# SigGenerator.net
KiCad netlist of a schematic drawn in EAGLE
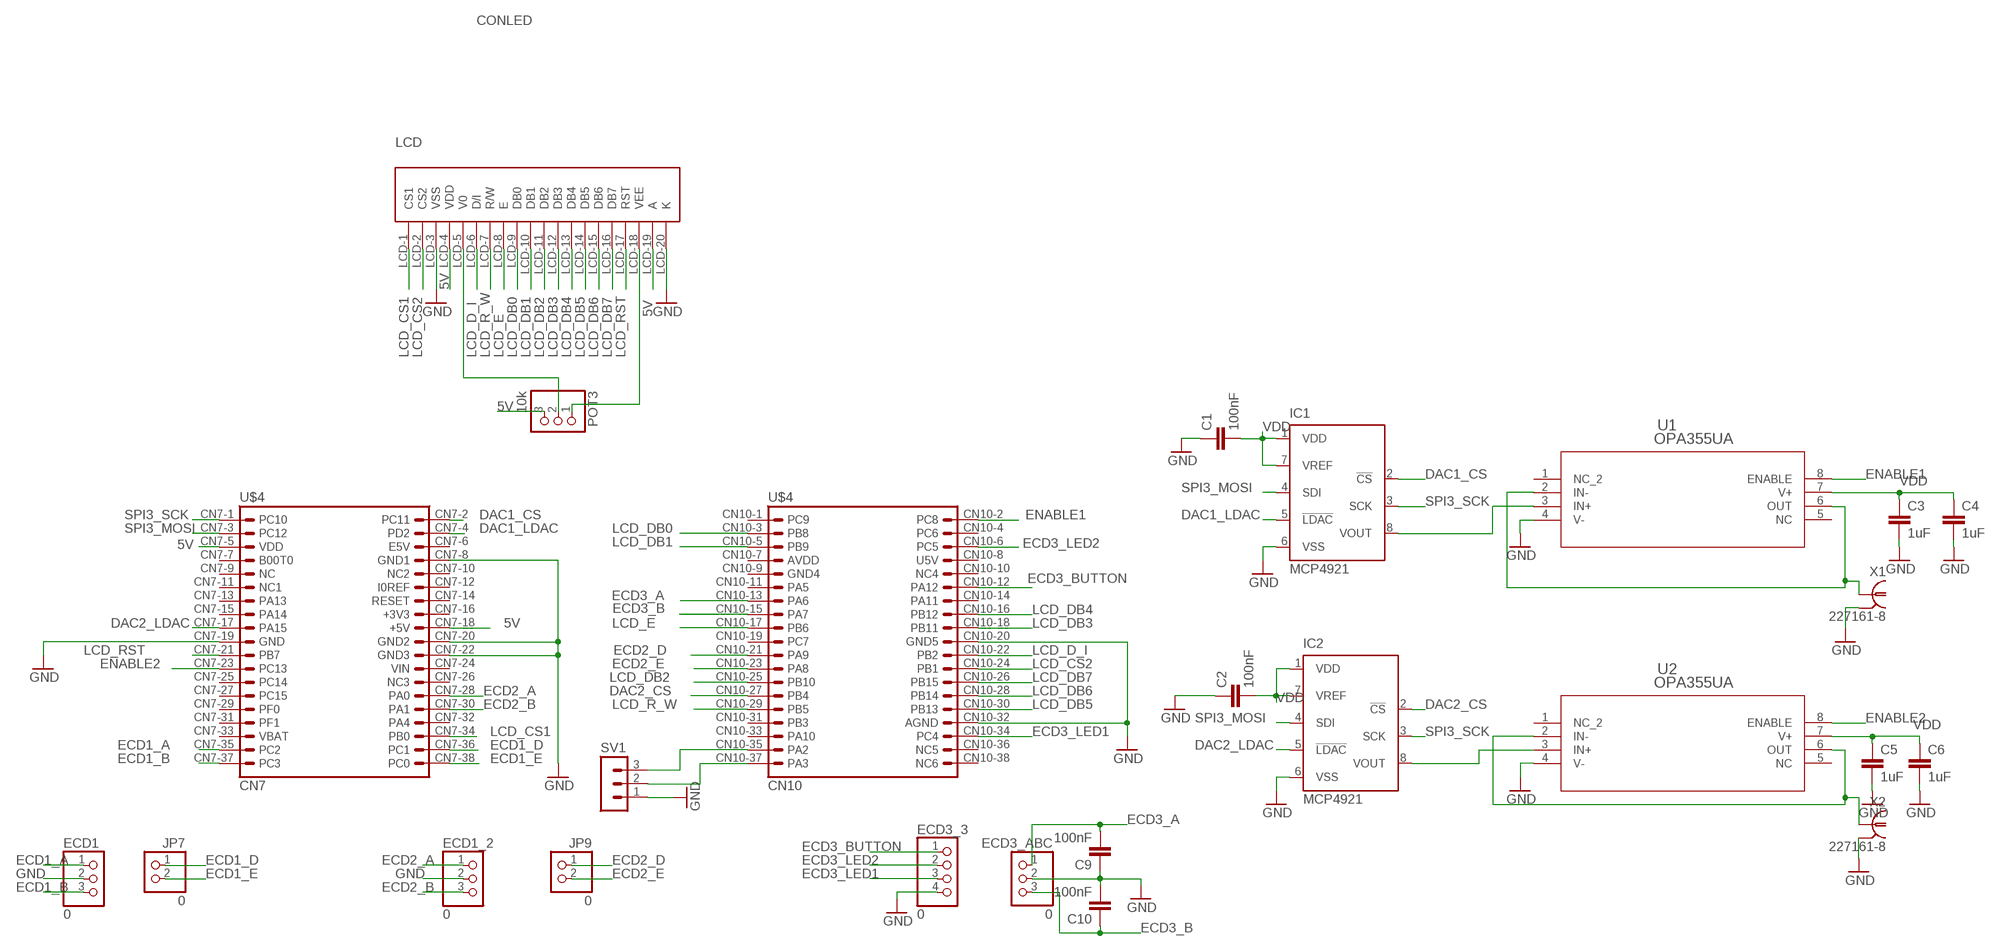
[diagram p0: schematic, sheet 1]
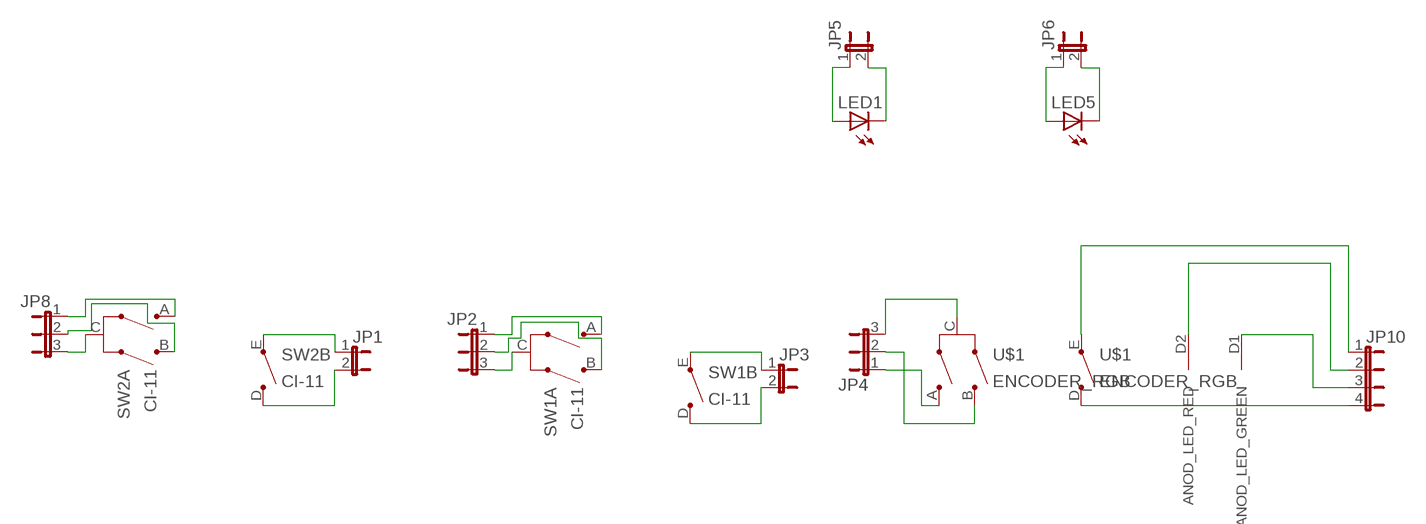
[diagram p1: schematic, sheet 2]

(export (version "E")
  (design (tool "Eeschema 10.0.6"))
  (components
    (comp (ref "JP1")
      (value "JP1E")
      (footprint "eagle-import:JP1")
      (libsource (lib "eagle-import") (part "JP1E"))
    )
    (comp (ref "JP2")
      (value "JP2E")
      (footprint "eagle-import:JP2")
      (libsource (lib "eagle-import") (part "JP2E"))
    )
    (comp (ref "JP3")
      (value "JP1E")
      (footprint "eagle-import:JP1")
      (libsource (lib "eagle-import") (part "JP1E"))
    )
    (comp (ref "JP4")
      (value "JP2E")
      (footprint "eagle-import:JP2")
      (libsource (lib "eagle-import") (part "JP2E"))
    )
    (comp (ref "JP5")
      (value "JP1E")
      (footprint "eagle-import:JP1")
      (libsource (lib "eagle-import") (part "JP1E"))
    )
    (comp (ref "JP6")
      (value "JP1E")
      (footprint "eagle-import:JP1")
      (libsource (lib "eagle-import") (part "JP1E"))
    )
    (comp (ref "JP8")
      (value "JP2E")
      (footprint "eagle-import:JP2")
      (libsource (lib "eagle-import") (part "JP2E"))
    )
    (comp (ref "JP10")
      (value "JP4E")
      (footprint "eagle-import:JP4")
      (libsource (lib "eagle-import") (part "JP4E"))
    )
    (comp (ref "LED1")
      (value "LEDSQR2X5")
      (footprint "eagle-import:LED2X5")
      (libsource (lib "eagle-import") (part "LEDSQR2X5"))
    )
    (comp (ref "LED5")
      (value "LEDSQR2X5")
      (footprint "eagle-import:LED2X5")
      (libsource (lib "eagle-import") (part "LEDSQR2X5"))
    )
    (comp (ref "SW1")
      (value "CI-11")
      (footprint "eagle-import:CI-11")
      (libsource (lib "eagle-import") (part "CI-11"))
    )
    (comp (ref "SW2")
      (value "CI-11")
      (footprint "eagle-import:CI-11")
      (libsource (lib "eagle-import") (part "CI-11"))
    )
    (comp (ref "U$1")
      (value "ENCODER_RGB")
      (footprint "eagle-import:ENCODER_RGB")
      (libsource (lib "eagle-import") (part "ENCODER_RGB"))
    )
    (comp (ref "C1")
      (value "100nF")
      (footprint "eagle-import:C2.5-3")
      (libsource (lib "eagle-import") (part "C2,5-3"))
    )
    (comp (ref "C2")
      (value "100nF")
      (footprint "eagle-import:C2.5-3")
      (libsource (lib "eagle-import") (part "C2,5-3"))
    )
    (comp (ref "C3")
      (value "1uF")
      (footprint "eagle-import:C2.5-3")
      (libsource (lib "eagle-import") (part "C2,5-3"))
    )
    (comp (ref "C4")
      (value "1uF")
      (footprint "eagle-import:C2.5-3")
      (libsource (lib "eagle-import") (part "C2,5-3"))
    )
    (comp (ref "C5")
      (value "1uF")
      (footprint "eagle-import:C2.5-3")
      (libsource (lib "eagle-import") (part "C2,5-3"))
    )
    (comp (ref "C6")
      (value "1uF")
      (footprint "eagle-import:C2.5-3")
      (libsource (lib "eagle-import") (part "C2,5-3"))
    )
    (comp (ref "C9")
      (value "100nF")
      (footprint "eagle-import:C2.5-3")
      (libsource (lib "eagle-import") (part "C2,5-3"))
    )
    (comp (ref "C10")
      (value "100nF")
      (footprint "eagle-import:C2.5-3")
      (libsource (lib "eagle-import") (part "C2,5-3"))
    )
    (comp (ref "ECD1")
      (value "0")
      (footprint "eagle-import:1X03")
      (libsource (lib "eagle-import") (part "PINHD-1X3"))
    )
    (comp (ref "ECD1_2")
      (value "0")
      (footprint "eagle-import:1X03")
      (libsource (lib "eagle-import") (part "PINHD-1X3"))
    )
    (comp (ref "ECD3_3")
      (value "0")
      (footprint "eagle-import:1X04")
      (libsource (lib "eagle-import") (part "PINHD-1X4"))
    )
    (comp (ref "ECD3_ABC")
      (value "0")
      (footprint "eagle-import:1X03")
      (libsource (lib "eagle-import") (part "PINHD-1X3"))
    )
    (comp (ref "IC1")
      (value "MCP4921")
      (footprint "eagle-import:DIL8")
      (libsource (lib "eagle-import") (part "MCP4921"))
    )
    (comp (ref "IC2")
      (value "MCP4921")
      (footprint "eagle-import:DIL8")
      (libsource (lib "eagle-import") (part "MCP4921"))
    )
    (comp (ref "JP7")
      (value "0")
      (footprint "eagle-import:1X02")
      (libsource (lib "eagle-import") (part "PINHD-1X2"))
    )
    (comp (ref "JP9")
      (value "0")
      (footprint "eagle-import:1X02")
      (libsource (lib "eagle-import") (part "PINHD-1X2"))
    )
    (comp (ref "LCD")
      (value "CONLED")
      (footprint "eagle-import:CONLCD")
      (libsource (lib "eagle-import") (part "CONLED"))
    )
    (comp (ref "POT3")
      (value "10k")
      (footprint "eagle-import:1X03")
      (libsource (lib "eagle-import") (part "PINHD-1X3"))
    )
    (comp (ref "SV1")
      (value "MA03-1")
      (footprint "eagle-import:MA03-1")
      (libsource (lib "eagle-import") (part "MA03-1"))
    )
    (comp (ref "U$4")
      (value "STM_MORPHO")
      (footprint "eagle-import:STM")
      (libsource (lib "eagle-import") (part "STM_MORPHO"))
    )
    (comp (ref "U1")
      (value "OPA355UA")
      (footprint "eagle-import:D8")
      (libsource (lib "eagle-import") (part "OPA355UA"))
    )
    (comp (ref "U2")
      (value "OPA355UA")
      (footprint "eagle-import:D8")
      (libsource (lib "eagle-import") (part "OPA355UA"))
    )
    (comp (ref "X1")
      (value "227161-8")
      (footprint "eagle-import:AMP_227161")
      (libsource (lib "eagle-import") (part "?227161-8"))
    )
    (comp (ref "X2")
      (value "227161-8")
      (footprint "eagle-import:AMP_227161")
      (libsource (lib "eagle-import") (part "?227161-8"))
    )
  )
  (nets
    (net (code "1") (name "5V") (class "Default")
      (node (ref "LCD") (pin "LCD-19") (pinfunction "A_LCD-19") (pintype "bidirectional"))
      (node (ref "LCD") (pin "LCD-4") (pinfunction "VDD_LCD-4") (pintype "bidirectional"))
      (node (ref "POT3") (pin "3") (pinfunction "3_3") (pintype "passive"))
      (node (ref "U$4") (pin "CN7-18") (pinfunction "+5V_CN7-18") (pintype "bidirectional"))
      (node (ref "U$4") (pin "CN7-5") (pinfunction "VDD_CN7-5") (pintype "bidirectional"))
    )
    (net (code "2") (name "DAC1_CS") (class "Default")
      (node (ref "IC1") (pin "2") (pinfunction "~{CS}_2") (pintype "input"))
      (node (ref "U$4") (pin "CN7-2") (pinfunction "PC11_CN7-2") (pintype "bidirectional"))
    )
    (net (code "3") (name "DAC1_LDAC") (class "Default")
      (node (ref "IC1") (pin "5") (pinfunction "~{LDAC}_5") (pintype "input"))
      (node (ref "U$4") (pin "CN7-4") (pinfunction "PD2_CN7-4") (pintype "bidirectional"))
    )
    (net (code "4") (name "DAC2_CS") (class "Default")
      (node (ref "IC2") (pin "2") (pinfunction "~{CS}_2") (pintype "input"))
      (node (ref "U$4") (pin "CN10-27") (pinfunction "PB4_CN10-27") (pintype "bidirectional"))
    )
    (net (code "5") (name "DAC2_LDAC") (class "Default")
      (node (ref "IC2") (pin "5") (pinfunction "~{LDAC}_5") (pintype "input"))
      (node (ref "U$4") (pin "CN7-17") (pinfunction "PA15_CN7-17") (pintype "bidirectional"))
    )
    (net (code "6") (name "ECD1_A") (class "Default")
      (node (ref "ECD1") (pin "1") (pinfunction "1_1") (pintype "passive"))
      (node (ref "U$4") (pin "CN7-35") (pinfunction "PC2_CN7-35") (pintype "bidirectional"))
    )
    (net (code "7") (name "ECD1_B") (class "Default")
      (node (ref "ECD1") (pin "3") (pinfunction "3_3") (pintype "passive"))
      (node (ref "U$4") (pin "CN7-37") (pinfunction "PC3_CN7-37") (pintype "bidirectional"))
    )
    (net (code "8") (name "ECD1_D") (class "Default")
      (node (ref "JP7") (pin "1") (pinfunction "1_1") (pintype "passive"))
      (node (ref "U$4") (pin "CN7-36") (pinfunction "PC1_CN7-36") (pintype "bidirectional"))
    )
    (net (code "9") (name "ECD1_E") (class "Default")
      (node (ref "JP7") (pin "2") (pinfunction "2_2") (pintype "passive"))
      (node (ref "U$4") (pin "CN7-38") (pinfunction "PC0_CN7-38") (pintype "bidirectional"))
    )
    (net (code "10") (name "ECD2_A") (class "Default")
      (node (ref "ECD1_2") (pin "1") (pinfunction "1_1") (pintype "passive"))
      (node (ref "U$4") (pin "CN7-28") (pinfunction "PA0_CN7-28") (pintype "bidirectional"))
    )
    (net (code "11") (name "ECD2_B") (class "Default")
      (node (ref "ECD1_2") (pin "3") (pinfunction "3_3") (pintype "passive"))
      (node (ref "U$4") (pin "CN7-30") (pinfunction "PA1_CN7-30") (pintype "bidirectional"))
    )
    (net (code "12") (name "ECD2_D") (class "Default")
      (node (ref "JP9") (pin "1") (pinfunction "1_1") (pintype "passive"))
      (node (ref "U$4") (pin "CN10-21") (pinfunction "PA9_CN10-21") (pintype "bidirectional"))
    )
    (net (code "13") (name "ECD2_E") (class "Default")
      (node (ref "JP9") (pin "2") (pinfunction "2_2") (pintype "passive"))
      (node (ref "U$4") (pin "CN10-23") (pinfunction "PA8_CN10-23") (pintype "bidirectional"))
    )
    (net (code "14") (name "ECD3_A") (class "Default")
      (node (ref "C9") (pin "2") (pinfunction "2_2") (pintype "passive"))
      (node (ref "ECD3_ABC") (pin "1") (pinfunction "1_1") (pintype "passive"))
      (node (ref "U$4") (pin "CN10-13") (pinfunction "PA6_CN10-13") (pintype "bidirectional"))
    )
    (net (code "15") (name "ECD3_B") (class "Default")
      (node (ref "C10") (pin "1") (pinfunction "1_1") (pintype "passive"))
      (node (ref "ECD3_ABC") (pin "3") (pinfunction "3_3") (pintype "passive"))
      (node (ref "U$4") (pin "CN10-15") (pinfunction "PA7_CN10-15") (pintype "bidirectional"))
    )
    (net (code "16") (name "ECD3_BUTTON") (class "Default")
      (node (ref "ECD3_3") (pin "1") (pinfunction "1_1") (pintype "passive"))
      (node (ref "U$4") (pin "CN10-12") (pinfunction "PA12_CN10-12") (pintype "bidirectional"))
    )
    (net (code "17") (name "ECD3_LED1") (class "Default")
      (node (ref "ECD3_3") (pin "3") (pinfunction "3_3") (pintype "passive"))
      (node (ref "U$4") (pin "CN10-34") (pinfunction "PC4_CN10-34") (pintype "bidirectional"))
    )
    (net (code "18") (name "ECD3_LED2") (class "Default")
      (node (ref "ECD3_3") (pin "2") (pinfunction "2_2") (pintype "passive"))
      (node (ref "U$4") (pin "CN10-6") (pinfunction "PC5_CN10-6") (pintype "bidirectional"))
    )
    (net (code "19") (name "ENABLE1") (class "Default")
      (node (ref "U$4") (pin "CN10-2") (pinfunction "PC8_CN10-2") (pintype "bidirectional"))
      (node (ref "U1") (pin "8") (pinfunction "ENABLE_8") (pintype "passive"))
    )
    (net (code "20") (name "ENABLE2") (class "Default")
      (node (ref "U$4") (pin "CN7-23") (pinfunction "PC13_CN7-23") (pintype "bidirectional"))
      (node (ref "U2") (pin "8") (pinfunction "ENABLE_8") (pintype "passive"))
    )
    (net (code "21") (name "GND") (class "Default")
      (node (ref "C1") (pin "1") (pinfunction "1_1") (pintype "passive"))
      (node (ref "C10") (pin "2") (pinfunction "2_2") (pintype "passive"))
      (node (ref "C2") (pin "1") (pinfunction "1_1") (pintype "passive"))
      (node (ref "C3") (pin "2") (pinfunction "2_2") (pintype "passive"))
      (node (ref "C4") (pin "2") (pinfunction "2_2") (pintype "passive"))
      (node (ref "C5") (pin "2") (pinfunction "2_2") (pintype "passive"))
      (node (ref "C6") (pin "2") (pinfunction "2_2") (pintype "passive"))
      (node (ref "C9") (pin "1") (pinfunction "1_1") (pintype "passive"))
      (node (ref "ECD1") (pin "2") (pinfunction "2_2") (pintype "passive"))
      (node (ref "ECD1_2") (pin "2") (pinfunction "2_2") (pintype "passive"))
      (node (ref "ECD3_3") (pin "4") (pinfunction "4_4") (pintype "passive"))
      (node (ref "ECD3_ABC") (pin "2") (pinfunction "2_2") (pintype "passive"))
      (node (ref "IC1") (pin "6") (pinfunction "VSS_6") (pintype "power_in"))
      (node (ref "IC2") (pin "6") (pinfunction "VSS_6") (pintype "power_in"))
      (node (ref "LCD") (pin "LCD-20") (pinfunction "K_LCD-20") (pintype "bidirectional"))
      (node (ref "LCD") (pin "LCD-3") (pinfunction "VSS_LCD-3") (pintype "bidirectional"))
      (node (ref "SV1") (pin "1") (pinfunction "1_1") (pintype "passive"))
      (node (ref "U$4") (pin "CN10-20") (pinfunction "GND5_CN10-20") (pintype "bidirectional"))
      (node (ref "U$4") (pin "CN10-32") (pinfunction "AGND_CN10-32") (pintype "bidirectional"))
      (node (ref "U$4") (pin "CN7-19") (pinfunction "GND_CN7-19") (pintype "bidirectional"))
      (node (ref "U$4") (pin "CN7-20") (pinfunction "GND2_CN7-20") (pintype "bidirectional"))
      (node (ref "U$4") (pin "CN7-22") (pinfunction "GND3_CN7-22") (pintype "bidirectional"))
      (node (ref "U$4") (pin "CN7-8") (pinfunction "GND1_CN7-8") (pintype "bidirectional"))
      (node (ref "U1") (pin "4") (pinfunction "V-_4") (pintype "power_in"))
      (node (ref "U2") (pin "4") (pinfunction "V-_4") (pintype "power_in"))
      (node (ref "X1") (pin "2") (pinfunction "2_2") (pintype "passive"))
      (node (ref "X2") (pin "2") (pinfunction "2_2") (pintype "passive"))
    )
    (net (code "22") (name "GND3") (class "Default")
      (node (ref "JP1") (pin "2") (pinfunction "2_2") (pintype "passive"))
      (node (ref "JP10") (pin "4") (pinfunction "4_4") (pintype "passive"))
      (node (ref "JP2") (pin "3") (pinfunction "3_3") (pintype "passive"))
      (node (ref "JP3") (pin "2") (pinfunction "2_2") (pintype "passive"))
      (node (ref "JP4") (pin "3") (pinfunction "3_3") (pintype "passive"))
      (node (ref "SW1") (pin "C") (pinfunction "C_C") (pintype "passive"))
      (node (ref "SW1") (pin "D") (pinfunction "D_D") (pintype "passive"))
      (node (ref "SW2") (pin "D") (pinfunction "D_D") (pintype "passive"))
      (node (ref "U$1") (pin "C") (pinfunction "C_C") (pintype "passive"))
      (node (ref "U$1") (pin "D") (pinfunction "1_D") (pintype "passive"))
    )
    (net (code "23") (name "LCD_CS1") (class "Default")
      (node (ref "LCD") (pin "LCD-1") (pinfunction "CS1_LCD-1") (pintype "bidirectional"))
      (node (ref "U$4") (pin "CN7-34") (pinfunction "PB0_CN7-34") (pintype "bidirectional"))
    )
    (net (code "24") (name "LCD_CS2") (class "Default")
      (node (ref "LCD") (pin "LCD-2") (pinfunction "CS2_LCD-2") (pintype "bidirectional"))
      (node (ref "U$4") (pin "CN10-24") (pinfunction "PB1_CN10-24") (pintype "bidirectional"))
    )
    (net (code "25") (name "LCD_DB0") (class "Default")
      (node (ref "LCD") (pin "LCD-9") (pinfunction "DB0_LCD-9") (pintype "bidirectional"))
      (node (ref "U$4") (pin "CN10-3") (pinfunction "PB8_CN10-3") (pintype "bidirectional"))
    )
    (net (code "26") (name "LCD_DB1") (class "Default")
      (node (ref "LCD") (pin "LCD-10") (pinfunction "DB1_LCD-10") (pintype "bidirectional"))
      (node (ref "U$4") (pin "CN10-5") (pinfunction "PB9_CN10-5") (pintype "bidirectional"))
    )
    (net (code "27") (name "LCD_DB2") (class "Default")
      (node (ref "LCD") (pin "LCD-11") (pinfunction "DB2_LCD-11") (pintype "bidirectional"))
      (node (ref "U$4") (pin "CN10-25") (pinfunction "PB10_CN10-25") (pintype "bidirectional"))
    )
    (net (code "28") (name "LCD_DB3") (class "Default")
      (node (ref "LCD") (pin "LCD-12") (pinfunction "DB3_LCD-12") (pintype "bidirectional"))
      (node (ref "U$4") (pin "CN10-18") (pinfunction "PB11_CN10-18") (pintype "bidirectional"))
    )
    (net (code "29") (name "LCD_DB4") (class "Default")
      (node (ref "LCD") (pin "LCD-13") (pinfunction "DB4_LCD-13") (pintype "bidirectional"))
      (node (ref "U$4") (pin "CN10-16") (pinfunction "PB12_CN10-16") (pintype "bidirectional"))
    )
    (net (code "30") (name "LCD_DB5") (class "Default")
      (node (ref "LCD") (pin "LCD-14") (pinfunction "DB5_LCD-14") (pintype "bidirectional"))
      (node (ref "U$4") (pin "CN10-30") (pinfunction "PB13_CN10-30") (pintype "bidirectional"))
    )
    (net (code "31") (name "LCD_DB6") (class "Default")
      (node (ref "LCD") (pin "LCD-15") (pinfunction "DB6_LCD-15") (pintype "bidirectional"))
      (node (ref "U$4") (pin "CN10-28") (pinfunction "PB14_CN10-28") (pintype "bidirectional"))
    )
    (net (code "32") (name "LCD_DB7") (class "Default")
      (node (ref "LCD") (pin "LCD-16") (pinfunction "DB7_LCD-16") (pintype "bidirectional"))
      (node (ref "U$4") (pin "CN10-26") (pinfunction "PB15_CN10-26") (pintype "bidirectional"))
    )
    (net (code "33") (name "LCD_D_I") (class "Default")
      (node (ref "LCD") (pin "LCD-6") (pinfunction "D/I_LCD-6") (pintype "bidirectional"))
      (node (ref "U$4") (pin "CN10-22") (pinfunction "PB2_CN10-22") (pintype "bidirectional"))
    )
    (net (code "34") (name "LCD_E") (class "Default")
      (node (ref "LCD") (pin "LCD-8") (pinfunction "E_LCD-8") (pintype "bidirectional"))
      (node (ref "U$4") (pin "CN10-17") (pinfunction "PB6_CN10-17") (pintype "bidirectional"))
    )
    (net (code "35") (name "LCD_RST") (class "Default")
      (node (ref "LCD") (pin "LCD-17") (pinfunction "RST_LCD-17") (pintype "bidirectional"))
      (node (ref "U$4") (pin "CN7-21") (pinfunction "PB7_CN7-21") (pintype "bidirectional"))
    )
    (net (code "36") (name "LCD_R_W") (class "Default")
      (node (ref "LCD") (pin "LCD-7") (pinfunction "R/W_LCD-7") (pintype "bidirectional"))
      (node (ref "U$4") (pin "CN10-29") (pinfunction "PB5_CN10-29") (pintype "bidirectional"))
    )
    (net (code "37") (name "Net-(IC1-VOUT)") (class "Default")
      (node (ref "IC1") (pin "8") (pinfunction "VOUT_8") (pintype "output"))
      (node (ref "U1") (pin "3") (pinfunction "IN+_3") (pintype "input"))
    )
    (net (code "38") (name "Net-(IC2-VOUT)") (class "Default")
      (node (ref "IC2") (pin "8") (pinfunction "VOUT_8") (pintype "output"))
      (node (ref "U2") (pin "3") (pinfunction "IN+_3") (pintype "input"))
    )
    (net (code "39") (name "Net-(JP1-Pad1)") (class "Default")
      (node (ref "JP1") (pin "1") (pinfunction "1_1") (pintype "passive"))
      (node (ref "SW2") (pin "E") (pinfunction "E_E") (pintype "passive"))
    )
    (net (code "40") (name "Net-(JP2-Pad1)") (class "Default")
      (node (ref "JP2") (pin "1") (pinfunction "1_1") (pintype "passive"))
      (node (ref "SW1") (pin "A") (pinfunction "A_A") (pintype "passive"))
    )
    (net (code "41") (name "Net-(JP2-Pad2)") (class "Default")
      (node (ref "JP2") (pin "2") (pinfunction "2_2") (pintype "passive"))
      (node (ref "SW1") (pin "B") (pinfunction "B_B") (pintype "passive"))
    )
    (net (code "42") (name "Net-(JP3-Pad1)") (class "Default")
      (node (ref "JP3") (pin "1") (pinfunction "1_1") (pintype "passive"))
      (node (ref "SW1") (pin "E") (pinfunction "E_E") (pintype "passive"))
    )
    (net (code "43") (name "Net-(JP4-Pad1)") (class "Default")
      (node (ref "JP4") (pin "1") (pinfunction "1_1") (pintype "passive"))
      (node (ref "U$1") (pin "A") (pinfunction "A_A") (pintype "passive"))
    )
    (net (code "44") (name "Net-(JP4-Pad2)") (class "Default")
      (node (ref "JP4") (pin "2") (pinfunction "2_2") (pintype "passive"))
      (node (ref "U$1") (pin "B") (pinfunction "B_B") (pintype "passive"))
    )
    (net (code "45") (name "Net-(JP5-Pad1)") (class "Default")
      (node (ref "JP5") (pin "1") (pinfunction "1_1") (pintype "passive"))
      (node (ref "LED1") (pin "A") (pinfunction "A_A") (pintype "passive"))
    )
    (net (code "46") (name "Net-(JP6-Pad1)") (class "Default")
      (node (ref "JP6") (pin "1") (pinfunction "1_1") (pintype "passive"))
      (node (ref "LED5") (pin "A") (pinfunction "A_A") (pintype "passive"))
    )
    (net (code "47") (name "Net-(JP8-Pad1)") (class "Default")
      (node (ref "JP8") (pin "1") (pinfunction "1_1") (pintype "passive"))
      (node (ref "SW2") (pin "A") (pinfunction "A_A") (pintype "passive"))
    )
    (net (code "48") (name "Net-(JP8-Pad2)") (class "Default")
      (node (ref "JP8") (pin "2") (pinfunction "2_2") (pintype "passive"))
      (node (ref "SW2") (pin "B") (pinfunction "B_B") (pintype "passive"))
    )
    (net (code "49") (name "Net-(JP8-Pad3)") (class "Default")
      (node (ref "JP8") (pin "3") (pinfunction "3_3") (pintype "passive"))
      (node (ref "SW2") (pin "C") (pinfunction "C_C") (pintype "passive"))
    )
    (net (code "50") (name "Net-(LCD-V0)") (class "Default")
      (node (ref "LCD") (pin "LCD-5") (pinfunction "V0_LCD-5") (pintype "bidirectional"))
      (node (ref "POT3") (pin "2") (pinfunction "2_2") (pintype "passive"))
    )
    (net (code "51") (name "Net-(LCD-VEE)") (class "Default")
      (node (ref "LCD") (pin "LCD-18") (pinfunction "VEE_LCD-18") (pintype "bidirectional"))
      (node (ref "POT3") (pin "1") (pinfunction "1_1") (pintype "passive"))
    )
    (net (code "52") (name "Net-(LED1-C)") (class "Default")
      (node (ref "JP5") (pin "2") (pinfunction "2_2") (pintype "passive"))
      (node (ref "LED1") (pin "K") (pinfunction "C_K") (pintype "passive"))
    )
    (net (code "53") (name "Net-(LED5-C)") (class "Default")
      (node (ref "JP6") (pin "2") (pinfunction "2_2") (pintype "passive"))
      (node (ref "LED5") (pin "K") (pinfunction "C_K") (pintype "passive"))
    )
    (net (code "54") (name "Net-(U$1-4)") (class "Default")
      (node (ref "JP10") (pin "1") (pinfunction "1_1") (pintype "passive"))
      (node (ref "U$1") (pin "E") (pinfunction "4_E") (pintype "passive"))
    )
    (net (code "55") (name "Net-(U$1-ANOD_LED_GREEN)") (class "Default")
      (node (ref "JP10") (pin "3") (pinfunction "3_3") (pintype "passive"))
      (node (ref "U$1") (pin "D1") (pinfunction "ANOD_LED_GREEN_D1") (pintype "bidirectional"))
    )
    (net (code "56") (name "Net-(U$1-ANOD_LED_RED)") (class "Default")
      (node (ref "JP10") (pin "2") (pinfunction "2_2") (pintype "passive"))
      (node (ref "U$1") (pin "D2") (pinfunction "ANOD_LED_RED_D2") (pintype "bidirectional"))
    )
    (net (code "57") (name "Net-(U$4-PA2)") (class "Default")
      (node (ref "SV1") (pin "3") (pinfunction "3_3") (pintype "passive"))
      (node (ref "U$4") (pin "CN10-35") (pinfunction "PA2_CN10-35") (pintype "bidirectional"))
    )
    (net (code "58") (name "Net-(U$4-PA3)") (class "Default")
      (node (ref "SV1") (pin "2") (pinfunction "2_2") (pintype "passive"))
      (node (ref "U$4") (pin "CN10-37") (pinfunction "PA3_CN10-37") (pintype "bidirectional"))
    )
    (net (code "59") (name "Net-(U1-IN-)") (class "Default")
      (node (ref "U1") (pin "2") (pinfunction "IN-_2") (pintype "input"))
      (node (ref "U1") (pin "6") (pinfunction "OUT_6") (pintype "output"))
      (node (ref "X1") (pin "1") (pinfunction "1_1") (pintype "passive"))
    )
    (net (code "60") (name "Net-(U2-IN-)") (class "Default")
      (node (ref "U2") (pin "2") (pinfunction "IN-_2") (pintype "input"))
      (node (ref "U2") (pin "6") (pinfunction "OUT_6") (pintype "output"))
      (node (ref "X2") (pin "1") (pinfunction "1_1") (pintype "passive"))
    )
    (net (code "61") (name "SPI3_MOSI") (class "Default")
      (node (ref "IC1") (pin "4") (pinfunction "SDI_4") (pintype "input"))
      (node (ref "IC2") (pin "4") (pinfunction "SDI_4") (pintype "input"))
      (node (ref "U$4") (pin "CN7-3") (pinfunction "PC12_CN7-3") (pintype "bidirectional"))
    )
    (net (code "62") (name "SPI3_SCK") (class "Default")
      (node (ref "IC1") (pin "3") (pinfunction "SCK_3") (pintype "input"))
      (node (ref "IC2") (pin "3") (pinfunction "SCK_3") (pintype "input"))
      (node (ref "U$4") (pin "CN7-1") (pinfunction "PC10_CN7-1") (pintype "bidirectional"))
    )
    (net (code "63") (name "VDD") (class "Default")
      (node (ref "C1") (pin "2") (pinfunction "2_2") (pintype "passive"))
      (node (ref "C2") (pin "2") (pinfunction "2_2") (pintype "passive"))
      (node (ref "C3") (pin "1") (pinfunction "1_1") (pintype "passive"))
      (node (ref "C4") (pin "1") (pinfunction "1_1") (pintype "passive"))
      (node (ref "C5") (pin "1") (pinfunction "1_1") (pintype "passive"))
      (node (ref "C6") (pin "1") (pinfunction "1_1") (pintype "passive"))
      (node (ref "IC1") (pin "1") (pinfunction "VDD_1") (pintype "power_in"))
      (node (ref "IC1") (pin "7") (pinfunction "VREF_7") (pintype "input"))
      (node (ref "IC2") (pin "1") (pinfunction "VDD_1") (pintype "power_in"))
      (node (ref "IC2") (pin "7") (pinfunction "VREF_7") (pintype "input"))
      (node (ref "U1") (pin "7") (pinfunction "V+_7") (pintype "power_in"))
      (node (ref "U2") (pin "7") (pinfunction "V+_7") (pintype "power_in"))
    )
    (net (code "64") (name "unconnected-(U$4-+3V3-PadCN7-16)") (class "Default")
      (node (ref "U$4") (pin "CN7-16") (pinfunction "+3V3_CN7-16") (pintype "bidirectional"))
    )
    (net (code "65") (name "unconnected-(U$4-AVDD-PadCN10-7)") (class "Default")
      (node (ref "U$4") (pin "CN10-7") (pinfunction "AVDD_CN10-7") (pintype "bidirectional"))
    )
    (net (code "66") (name "unconnected-(U$4-B00T0-PadCN7-7)") (class "Default")
      (node (ref "U$4") (pin "CN7-7") (pinfunction "B00T0_CN7-7") (pintype "bidirectional"))
    )
    (net (code "67") (name "unconnected-(U$4-E5V-PadCN7-6)") (class "Default")
      (node (ref "U$4") (pin "CN7-6") (pinfunction "E5V_CN7-6") (pintype "bidirectional"))
    )
    (net (code "68") (name "unconnected-(U$4-GND4-PadCN10-9)") (class "Default")
      (node (ref "U$4") (pin "CN10-9") (pinfunction "GND4_CN10-9") (pintype "bidirectional"))
    )
    (net (code "69") (name "unconnected-(U$4-I0REF-PadCN7-12)") (class "Default")
      (node (ref "U$4") (pin "CN7-12") (pinfunction "I0REF_CN7-12") (pintype "bidirectional"))
    )
    (net (code "70") (name "unconnected-(U$4-NC-PadCN7-9)") (class "Default")
      (node (ref "U$4") (pin "CN7-9") (pinfunction "NC_CN7-9") (pintype "bidirectional"))
    )
    (net (code "71") (name "unconnected-(U$4-NC1-PadCN7-11)") (class "Default")
      (node (ref "U$4") (pin "CN7-11") (pinfunction "NC1_CN7-11") (pintype "bidirectional"))
    )
    (net (code "72") (name "unconnected-(U$4-NC2-PadCN7-10)") (class "Default")
      (node (ref "U$4") (pin "CN7-10") (pinfunction "NC2_CN7-10") (pintype "bidirectional"))
    )
    (net (code "73") (name "unconnected-(U$4-NC3-PadCN7-26)") (class "Default")
      (node (ref "U$4") (pin "CN7-26") (pinfunction "NC3_CN7-26") (pintype "bidirectional"))
    )
    (net (code "74") (name "unconnected-(U$4-NC4-PadCN10-10)") (class "Default")
      (node (ref "U$4") (pin "CN10-10") (pinfunction "NC4_CN10-10") (pintype "bidirectional"))
    )
    (net (code "75") (name "unconnected-(U$4-NC5-PadCN10-36)") (class "Default")
      (node (ref "U$4") (pin "CN10-36") (pinfunction "NC5_CN10-36") (pintype "bidirectional"))
    )
    (net (code "76") (name "unconnected-(U$4-NC6-PadCN10-38)") (class "Default")
      (node (ref "U$4") (pin "CN10-38") (pinfunction "NC6_CN10-38") (pintype "bidirectional"))
    )
    (net (code "77") (name "unconnected-(U$4-PA4-PadCN7-32)") (class "Default")
      (node (ref "U$4") (pin "CN7-32") (pinfunction "PA4_CN7-32") (pintype "bidirectional"))
    )
    (net (code "78") (name "unconnected-(U$4-PA5-PadCN10-11)") (class "Default")
      (node (ref "U$4") (pin "CN10-11") (pinfunction "PA5_CN10-11") (pintype "bidirectional"))
    )
    (net (code "79") (name "unconnected-(U$4-PA10-PadCN10-33)") (class "Default")
      (node (ref "U$4") (pin "CN10-33") (pinfunction "PA10_CN10-33") (pintype "bidirectional"))
    )
    (net (code "80") (name "unconnected-(U$4-PA11-PadCN10-14)") (class "Default")
      (node (ref "U$4") (pin "CN10-14") (pinfunction "PA11_CN10-14") (pintype "bidirectional"))
    )
    (net (code "81") (name "unconnected-(U$4-PA13-PadCN7-13)") (class "Default")
      (node (ref "U$4") (pin "CN7-13") (pinfunction "PA13_CN7-13") (pintype "bidirectional"))
    )
    (net (code "82") (name "unconnected-(U$4-PA14-PadCN7-15)") (class "Default")
      (node (ref "U$4") (pin "CN7-15") (pinfunction "PA14_CN7-15") (pintype "bidirectional"))
    )
    (net (code "83") (name "unconnected-(U$4-PB3-PadCN10-31)") (class "Default")
      (node (ref "U$4") (pin "CN10-31") (pinfunction "PB3_CN10-31") (pintype "bidirectional"))
    )
    (net (code "84") (name "unconnected-(U$4-PC6-PadCN10-4)") (class "Default")
      (node (ref "U$4") (pin "CN10-4") (pinfunction "PC6_CN10-4") (pintype "bidirectional"))
    )
    (net (code "85") (name "unconnected-(U$4-PC7-PadCN10-19)") (class "Default")
      (node (ref "U$4") (pin "CN10-19") (pinfunction "PC7_CN10-19") (pintype "bidirectional"))
    )
    (net (code "86") (name "unconnected-(U$4-PC9-PadCN10-1)") (class "Default")
      (node (ref "U$4") (pin "CN10-1") (pinfunction "PC9_CN10-1") (pintype "bidirectional"))
    )
    (net (code "87") (name "unconnected-(U$4-PC14-PadCN7-25)") (class "Default")
      (node (ref "U$4") (pin "CN7-25") (pinfunction "PC14_CN7-25") (pintype "bidirectional"))
    )
    (net (code "88") (name "unconnected-(U$4-PC15-PadCN7-27)") (class "Default")
      (node (ref "U$4") (pin "CN7-27") (pinfunction "PC15_CN7-27") (pintype "bidirectional"))
    )
    (net (code "89") (name "unconnected-(U$4-PF0-PadCN7-29)") (class "Default")
      (node (ref "U$4") (pin "CN7-29") (pinfunction "PF0_CN7-29") (pintype "bidirectional"))
    )
    (net (code "90") (name "unconnected-(U$4-PF1-PadCN7-31)") (class "Default")
      (node (ref "U$4") (pin "CN7-31") (pinfunction "PF1_CN7-31") (pintype "bidirectional"))
    )
    (net (code "91") (name "unconnected-(U$4-RESET-PadCN7-14)") (class "Default")
      (node (ref "U$4") (pin "CN7-14") (pinfunction "RESET_CN7-14") (pintype "bidirectional"))
    )
    (net (code "92") (name "unconnected-(U$4-U5V-PadCN10-8)") (class "Default")
      (node (ref "U$4") (pin "CN10-8") (pinfunction "U5V_CN10-8") (pintype "bidirectional"))
    )
    (net (code "93") (name "unconnected-(U$4-VBAT-PadCN7-33)") (class "Default")
      (node (ref "U$4") (pin "CN7-33") (pinfunction "VBAT_CN7-33") (pintype "bidirectional"))
    )
    (net (code "94") (name "unconnected-(U$4-VIN-PadCN7-24)") (class "Default")
      (node (ref "U$4") (pin "CN7-24") (pinfunction "VIN_CN7-24") (pintype "bidirectional"))
    )
    (net (code "95") (name "unconnected-(U1-NC-Pad5)") (class "Default")
      (node (ref "U1") (pin "5") (pinfunction "NC_5") (pintype "no_connect"))
    )
    (net (code "96") (name "unconnected-(U1-NC_2-Pad1)") (class "Default")
      (node (ref "U1") (pin "1") (pinfunction "NC_2_1") (pintype "no_connect"))
    )
    (net (code "97") (name "unconnected-(U2-NC-Pad5)") (class "Default")
      (node (ref "U2") (pin "5") (pinfunction "NC_5") (pintype "no_connect"))
    )
    (net (code "98") (name "unconnected-(U2-NC_2-Pad1)") (class "Default")
      (node (ref "U2") (pin "1") (pinfunction "NC_2_1") (pintype "no_connect"))
    )
  )
)
